# USB-RS485_mini.net
KiCad netlist of a schematic drawn in Altium Designer
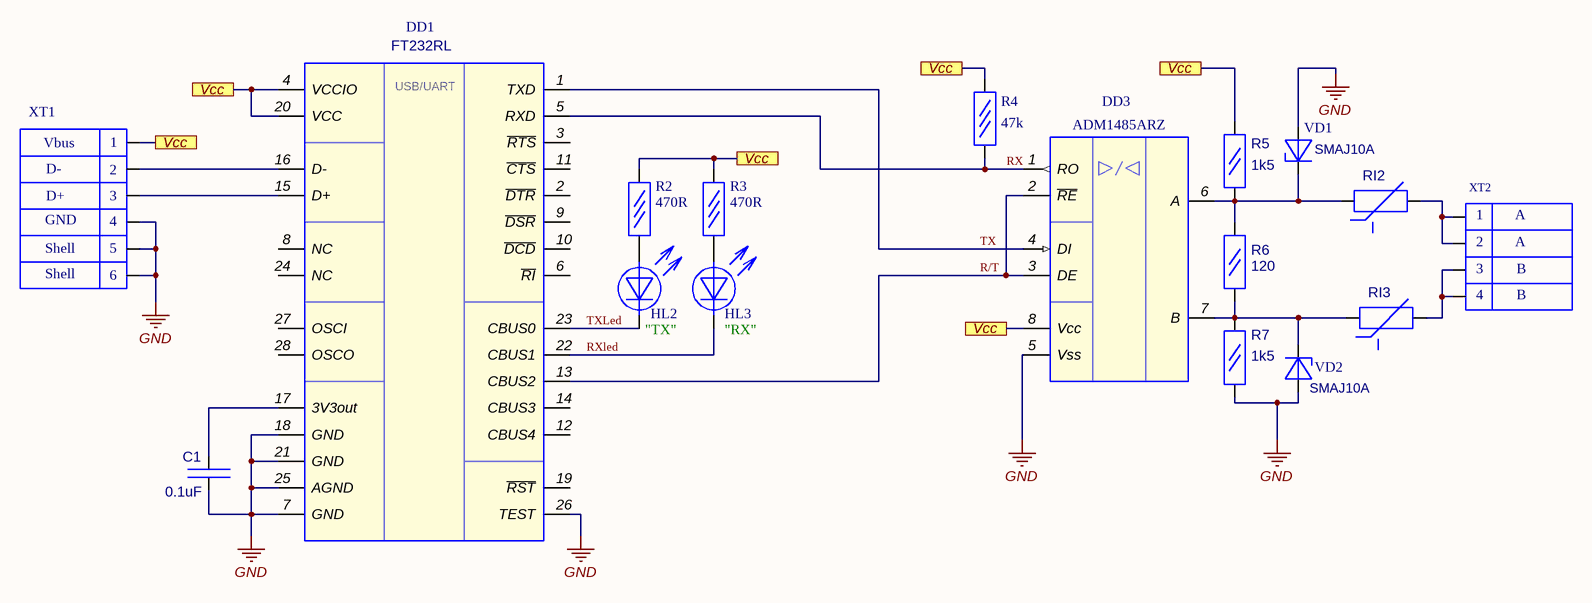
[diagram p0: USB-RS485_mini.SchDoc]

(export (version "E")
  (design (tool "Eeschema 10.0.6"))
  (components
    (comp (ref "C1")
      (value "0.1uF")
      (footprint "1608[0603]")
      (description "Capacitor GOST")
      (fields (field (name "VOLTAGE") "25V") (field (name "TOLERANCE") "5%/10%"))
      (libsource (lib "General Devices (laz)") (part "Cap1"))
    )
    (comp (ref "DD1")
      (value "FT232RL")
      (footprint "SSOP28")
      (description "USB/UART")
      (libsource (lib "General Devices (laz)") (part "FT232RL"))
    )
    (comp (ref "DD3")
      (value "ADM1485ARZ")
      (footprint "SO8_M")
      (description "MAX483EESA")
      (fields (field (name "Comment") "MAX48xx"))
      (libsource (lib "General Devices (laz)") (part "MAX48xx"))
    )
    (comp (ref "HL2")
      (value "LED1_Gost_2")
      (footprint "LED_R- 0603")
      (description "Nichia157 LED")
      (libsource (lib "General Devices (laz)") (part "LED1_Gost_2"))
    )
    (comp (ref "HL3")
      (value "LED1_Gost_2")
      (footprint "LED_Y- 0603")
      (description "Nichia157 LED")
      (libsource (lib "General Devices (laz)") (part "LED1_Gost_2"))
    )
    (comp (ref "R2")
      (value "470R")
      (footprint "RESC1608(0603)")
      (description "CR0603 GOST")
      (fields (field (name "Comment") "Res 1/16W"))
      (libsource (lib "General Devices (laz)") (part "Res 1/16W"))
    )
    (comp (ref "R3")
      (value "470R")
      (footprint "RESC1608(0603)")
      (description "CR0603 GOST")
      (fields (field (name "Comment") "Res 1/16W"))
      (libsource (lib "General Devices (laz)") (part "Res 1/16W"))
    )
    (comp (ref "R4")
      (value "47k")
      (footprint "RESC1608(0603)")
      (description "CR0603 GOST")
      (fields (field (name "Comment") "Res 1/16W"))
      (libsource (lib "General Devices (laz)") (part "Res 1/16W"))
    )
    (comp (ref "R5")
      (value "1k5")
      (footprint "RESC2012(0805)")
      (description "Resistor GOST")
      (fields (field (name "TOLERANCE") "10%") (field (name "Comment") "Res 1/8W"))
      (libsource (lib "") (part "Res 1/8W_1"))
    )
    (comp (ref "R6")
      (value "120")
      (footprint "RESC2012(0805)")
      (description "Resistor GOST")
      (fields (field (name "TOLERANCE") "10%") (field (name "Comment") "Res 1/8W"))
      (libsource (lib "General Devices (laz)") (part "Res 1/8W"))
    )
    (comp (ref "R7")
      (value "1k5")
      (footprint "RESC2012(0805)")
      (description "Resistor GOST")
      (fields (field (name "TOLERANCE") "10%") (field (name "Comment") "Res 1/8W"))
      (libsource (lib "") (part "Res 1/8W_1"))
    )
    (comp (ref "RI2")
      (value "MF-MSMF010")
      (footprint "Fuse 1206")
      (description "MultiFuse")
      (libsource (lib "General Devices (laz)") (part "MF-MSMF010"))
    )
    (comp (ref "RI3")
      (value "MF-MSMF010")
      (footprint "Fuse 1206")
      (description "MultiFuse")
      (libsource (lib "General Devices (laz)") (part "MF-MSMF010"))
    )
    (comp (ref "VD1")
      (value "SMAJ10A")
      (footprint "SMA (DO-214AC)")
      (description "Diode Zener GOST")
      (fields (field (name "Comment") "Diode Zener"))
      (libsource (lib "General Devices (laz)") (part "Diode Zener"))
    )
    (comp (ref "VD2")
      (value "SMAJ10A")
      (footprint "SMA (DO-214AC)")
      (description "Diode Zener GOST")
      (fields (field (name "Comment") "Diode Zener"))
      (libsource (lib "General Devices (laz)") (part "Diode Zener"))
    )
    (comp (ref "XT1")
      (value "Connect x6")
      (footprint "USB-AR")
      (description "USB")
      (libsource (lib "General Devices (laz)") (part "Connect x6"))
    )
    (comp (ref "XT2")
      (value "Connect x4_mini")
      (footprint "Term. Block-4pin")
      (description "2xRS485")
      (libsource (lib "General Devices (laz)") (part "Connect x4_mini"))
    )
  )
  (nets
    (net (code "1") (name "/RX") (class "Default")
      (node (ref "DD1") (pin "5") (pinfunction "RXD_5") (pintype "passive"))
      (node (ref "DD3") (pin "1") (pinfunction "RO_1") (pintype "output"))
      (node (ref "R4") (pin "1") (pinfunction "1_1") (pintype "passive"))
    )
    (net (code "2") (name "/RXled") (class "Default")
      (node (ref "DD1") (pin "22") (pinfunction "CBUS1_22") (pintype "passive"))
      (node (ref "HL3") (pin "2") (pinfunction "2_2") (pintype "passive"))
    )
    (net (code "3") (name "/R{slash}T") (class "Default")
      (node (ref "DD1") (pin "13") (pinfunction "CBUS2_13") (pintype "passive"))
      (node (ref "DD3") (pin "2") (pinfunction "~{RE}_2") (pintype "passive"))
      (node (ref "DD3") (pin "3") (pinfunction "DE_3") (pintype "passive"))
    )
    (net (code "4") (name "/TX") (class "Default")
      (node (ref "DD1") (pin "1") (pinfunction "TXD_1") (pintype "passive"))
      (node (ref "DD3") (pin "4") (pinfunction "DI_4") (pintype "input"))
    )
    (net (code "5") (name "/TXLed") (class "Default")
      (node (ref "DD1") (pin "23") (pinfunction "CBUS0_23") (pintype "passive"))
      (node (ref "HL2") (pin "2") (pinfunction "2_2") (pintype "passive"))
    )
    (net (code "6") (name "/Vcc") (class "Default")
      (node (ref "DD1") (pin "20") (pinfunction "VCC_20") (pintype "passive"))
      (node (ref "DD1") (pin "4") (pinfunction "VCCIO_4") (pintype "passive"))
      (node (ref "DD3") (pin "8") (pinfunction "Vcc_8") (pintype "passive"))
      (node (ref "R2") (pin "2") (pinfunction "2_2") (pintype "passive"))
      (node (ref "R3") (pin "2") (pinfunction "2_2") (pintype "passive"))
      (node (ref "R4") (pin "2") (pinfunction "2_2") (pintype "passive"))
      (node (ref "R5") (pin "1") (pinfunction "1_1") (pintype "passive"))
      (node (ref "XT1") (pin "1") (pinfunction "1_1") (pintype "passive"))
    )
    (net (code "7") (name "GND") (class "Default")
      (node (ref "C1") (pin "1") (pinfunction "1_1") (pintype "passive"))
      (node (ref "DD1") (pin "18") (pinfunction "GND_18") (pintype "passive"))
      (node (ref "DD1") (pin "21") (pinfunction "GND_21") (pintype "passive"))
      (node (ref "DD1") (pin "25") (pinfunction "AGND_25") (pintype "passive"))
      (node (ref "DD1") (pin "26") (pinfunction "TEST_26") (pintype "passive"))
      (node (ref "DD1") (pin "7") (pinfunction "GND_7") (pintype "passive"))
      (node (ref "DD3") (pin "5") (pinfunction "Vss_5") (pintype "passive"))
      (node (ref "R7") (pin "2") (pinfunction "2_2") (pintype "passive"))
      (node (ref "VD1") (pin "1") (pinfunction "1_1") (pintype "passive"))
      (node (ref "VD2") (pin "1") (pinfunction "1_1") (pintype "passive"))
      (node (ref "XT1") (pin "4") (pinfunction "4_4") (pintype "passive"))
      (node (ref "XT1") (pin "5") (pinfunction "5_5") (pintype "passive"))
      (node (ref "XT1") (pin "6") (pinfunction "6_6") (pintype "passive"))
    )
    (net (code "8") (name "Net-(DD1-3V3out)") (class "Default")
      (node (ref "C1") (pin "2") (pinfunction "2_2") (pintype "passive"))
      (node (ref "DD1") (pin "17") (pinfunction "3V3out_17") (pintype "passive"))
    )
    (net (code "9") (name "Net-(DD1-D+)") (class "Default")
      (node (ref "DD1") (pin "15") (pinfunction "D+_15") (pintype "passive"))
      (node (ref "XT1") (pin "3") (pinfunction "3_3") (pintype "passive"))
    )
    (net (code "10") (name "Net-(DD1-D-)") (class "Default")
      (node (ref "DD1") (pin "16") (pinfunction "D-_16") (pintype "passive"))
      (node (ref "XT1") (pin "2") (pinfunction "2_2") (pintype "passive"))
    )
    (net (code "11") (name "Net-(DD3-A)") (class "Default")
      (node (ref "DD3") (pin "6") (pinfunction "A_6") (pintype "passive"))
      (node (ref "R5") (pin "2") (pinfunction "2_2") (pintype "passive"))
      (node (ref "R6") (pin "2") (pinfunction "2_2") (pintype "passive"))
      (node (ref "RI2") (pin "2") (pinfunction "2_2") (pintype "passive"))
      (node (ref "VD1") (pin "2") (pinfunction "2_2") (pintype "passive"))
    )
    (net (code "12") (name "Net-(DD3-B)") (class "Default")
      (node (ref "DD3") (pin "7") (pinfunction "B_7") (pintype "passive"))
      (node (ref "R6") (pin "1") (pinfunction "1_1") (pintype "passive"))
      (node (ref "R7") (pin "1") (pinfunction "1_1") (pintype "passive"))
      (node (ref "RI3") (pin "2") (pinfunction "2_2") (pintype "passive"))
      (node (ref "VD2") (pin "2") (pinfunction "2_2") (pintype "passive"))
    )
    (net (code "13") (name "Net-(HL2-Pad1)") (class "Default")
      (node (ref "HL2") (pin "1") (pinfunction "1_1") (pintype "passive"))
      (node (ref "R2") (pin "1") (pinfunction "1_1") (pintype "passive"))
    )
    (net (code "14") (name "Net-(HL3-Pad1)") (class "Default")
      (node (ref "HL3") (pin "1") (pinfunction "1_1") (pintype "passive"))
      (node (ref "R3") (pin "1") (pinfunction "1_1") (pintype "passive"))
    )
    (net (code "15") (name "Net-(RI2-Pad1)") (class "Default")
      (node (ref "RI2") (pin "1") (pinfunction "1_1") (pintype "passive"))
      (node (ref "XT2") (pin "1") (pinfunction "A_1") (pintype "passive"))
      (node (ref "XT2") (pin "2") (pinfunction "A_2") (pintype "passive"))
    )
    (net (code "16") (name "Net-(RI3-Pad1)") (class "Default")
      (node (ref "RI3") (pin "1") (pinfunction "1_1") (pintype "passive"))
      (node (ref "XT2") (pin "3") (pinfunction "B_3") (pintype "passive"))
      (node (ref "XT2") (pin "4") (pinfunction "B_4") (pintype "passive"))
    )
    (net (code "17") (name "unconnected-(DD1-CBUS3-Pad14)") (class "Default")
      (node (ref "DD1") (pin "14") (pinfunction "CBUS3_14") (pintype "passive"))
    )
    (net (code "18") (name "unconnected-(DD1-CBUS4-Pad12)") (class "Default")
      (node (ref "DD1") (pin "12") (pinfunction "CBUS4_12") (pintype "passive"))
    )
    (net (code "19") (name "unconnected-(DD1-NC-Pad8)") (class "Default")
      (node (ref "DD1") (pin "8") (pinfunction "NC_8") (pintype "passive"))
    )
    (net (code "20") (name "unconnected-(DD1-NC-Pad24)") (class "Default")
      (node (ref "DD1") (pin "24") (pinfunction "NC_24") (pintype "passive"))
    )
    (net (code "21") (name "unconnected-(DD1-OSCI-Pad27)") (class "Default")
      (node (ref "DD1") (pin "27") (pinfunction "OSCI_27") (pintype "passive"))
    )
    (net (code "22") (name "unconnected-(DD1-OSCO-Pad28)") (class "Default")
      (node (ref "DD1") (pin "28") (pinfunction "OSCO_28") (pintype "passive"))
    )
    (net (code "23") (name "unconnected-(DD1-~{CTS}-Pad11)") (class "Default")
      (node (ref "DD1") (pin "11") (pinfunction "~{CTS}_11") (pintype "passive"))
    )
    (net (code "24") (name "unconnected-(DD1-~{DCD}-Pad10)") (class "Default")
      (node (ref "DD1") (pin "10") (pinfunction "~{DCD}_10") (pintype "passive"))
    )
    (net (code "25") (name "unconnected-(DD1-~{DSR}-Pad9)") (class "Default")
      (node (ref "DD1") (pin "9") (pinfunction "~{DSR}_9") (pintype "passive"))
    )
    (net (code "26") (name "unconnected-(DD1-~{DTR}-Pad2)") (class "Default")
      (node (ref "DD1") (pin "2") (pinfunction "~{DTR}_2") (pintype "passive"))
    )
    (net (code "27") (name "unconnected-(DD1-~{RI}-Pad6)") (class "Default")
      (node (ref "DD1") (pin "6") (pinfunction "~{RI}_6") (pintype "passive"))
    )
    (net (code "28") (name "unconnected-(DD1-~{RST}-Pad19)") (class "Default")
      (node (ref "DD1") (pin "19") (pinfunction "~{RST}_19") (pintype "passive"))
    )
    (net (code "29") (name "unconnected-(DD1-~{RTS}-Pad3)") (class "Default")
      (node (ref "DD1") (pin "3") (pinfunction "~{RTS}_3") (pintype "passive"))
    )
  )
)
